# 08-DcMotorEncoder.net
KiCad netlist of a schematic drawn in Altium Designer
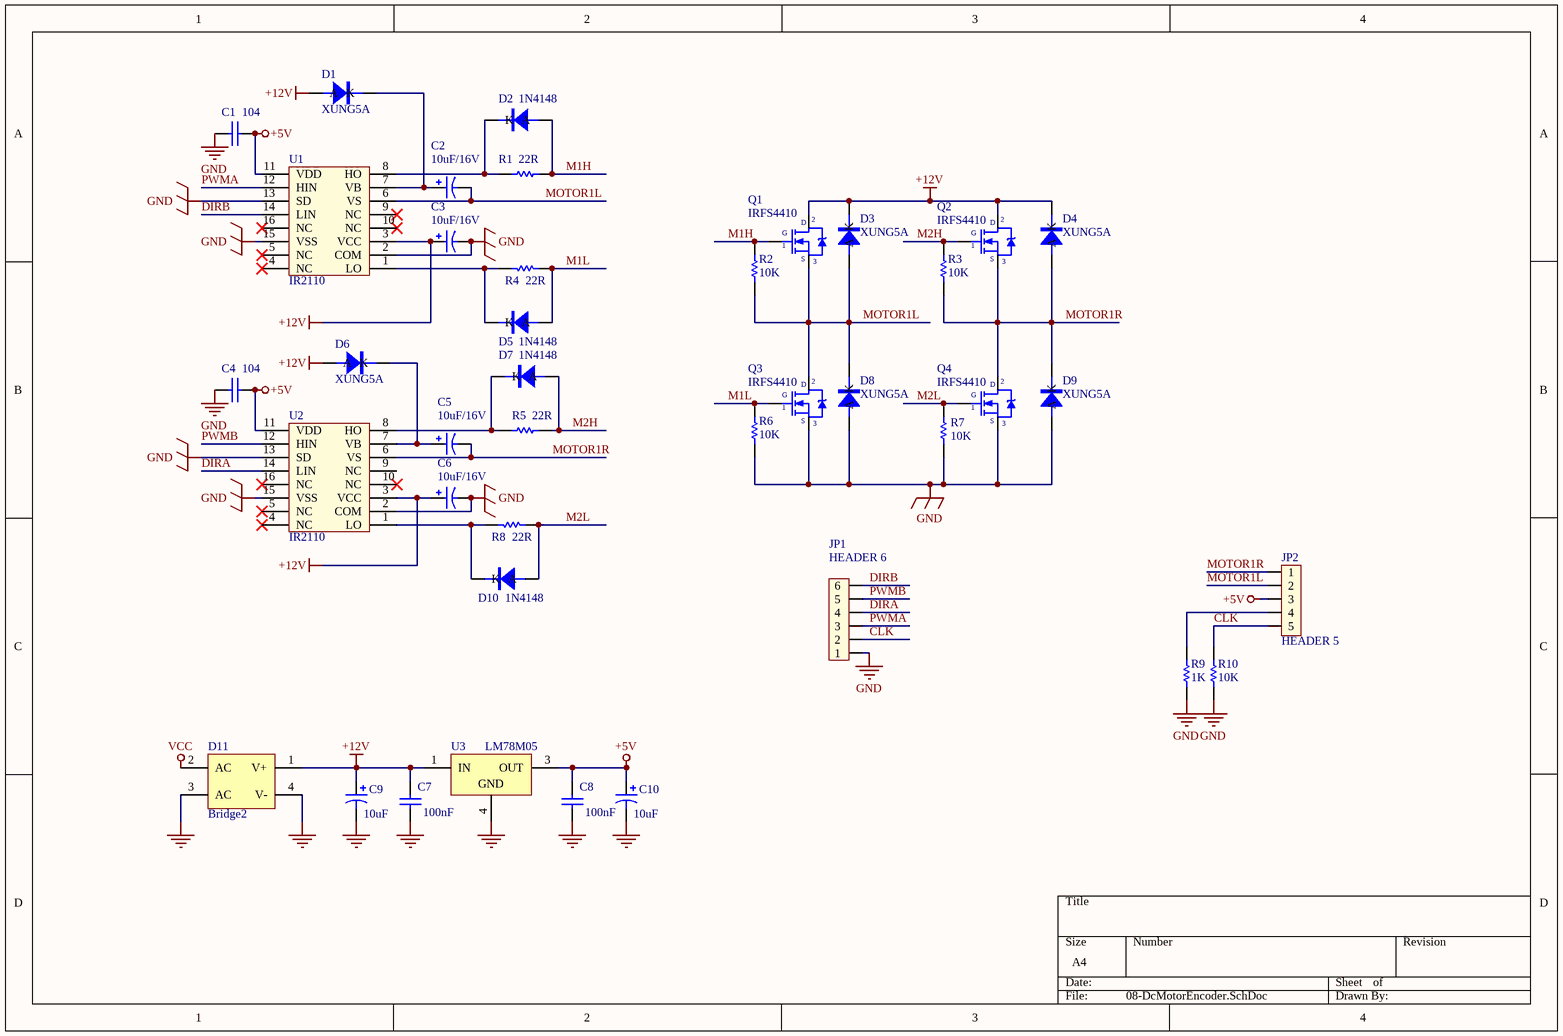
[diagram p0: 08-DcMotorEncoder.SchDoc]

(export (version "E")
  (design (tool "Eeschema 10.0.6"))
  (components
    (comp (ref "C1")
      (value "104")
      (footprint "R-0805")
      (fields (field (name "ALTIUM_VALUE") "104"))
      (libsource (lib "Maker") (part "CAP NP"))
    )
    (comp (ref "C2")
      (value "10uF/16V")
      (footprint "C-TANT-1210")
      (fields (field (name "Comment") "10U16V"))
      (libsource (lib "Maker") (part "CAP POL"))
    )
    (comp (ref "C3")
      (value "10uF/16V")
      (footprint "C-TANT-1210")
      (fields (field (name "Comment") "10U16V"))
      (libsource (lib "Maker") (part "CAP POL"))
    )
    (comp (ref "C4")
      (value "104")
      (footprint "R-0805")
      (fields (field (name "ALTIUM_VALUE") "104"))
      (libsource (lib "Maker") (part "CAP NP"))
    )
    (comp (ref "C5")
      (value "10uF/16V")
      (footprint "C-TANT-1210")
      (fields (field (name "Comment") "10U16V"))
      (libsource (lib "Maker") (part "CAP POL"))
    )
    (comp (ref "C6")
      (value "10uF/16V")
      (footprint "C-TANT-1210")
      (fields (field (name "Comment") "10U16V"))
      (libsource (lib "Maker") (part "CAP POL"))
    )
    (comp (ref "C7")
      (value "100nF")
      (footprint "RAD-0.3")
      (description "Capacitor")
      (fields (field (name "Comment") "104") (field (name "PUBLISHER") "Altium Limited"))
      (libsource (lib "Miscellaneous Devices") (part "Cap"))
    )
    (comp (ref "C8")
      (value "100nF")
      (footprint "RAD-0.3")
      (description "Capacitor")
      (fields (field (name "Comment") "104") (field (name "PUBLISHER") "Altium Limited"))
      (libsource (lib "Miscellaneous Devices") (part "Cap"))
    )
    (comp (ref "C9")
      (value "10uF")
      (footprint "RB7.6-15")
      (description "Polarized Capacitor (Radial)")
      (fields (field (name "Comment") "10uF/16V") (field (name "PUBLISHER") "Altium Limited"))
      (libsource (lib "Miscellaneous Devices") (part "Cap Pol1"))
    )
    (comp (ref "C10")
      (value "10uF")
      (footprint "RB7.6-15")
      (description "Polarized Capacitor (Radial)")
      (fields (field (name "Comment") "10uF/16V") (field (name "PUBLISHER") "Altium Limited"))
      (libsource (lib "Miscellaneous Devices") (part "Cap Pol1"))
    )
    (comp (ref "D1")
      (value "XUNG5A")
      (footprint "D-DO214-AC")
      (fields (field (name "Comment") "1N4007"))
      (libsource (lib "") (part "DIODE_3"))
    )
    (comp (ref "D2") (value "1N4148") (footprint "D-DO213-AA") (libsource (lib "") (part "DIODE_1")))
    (comp (ref "D3")
      (value "XUNG5A")
      (footprint "D-DO214-AC")
      (fields (field (name "Comment") "1N4007"))
      (libsource (lib "Maker") (part "DIODE"))
    )
    (comp (ref "D4")
      (value "XUNG5A")
      (footprint "D-DO214-AC")
      (fields (field (name "Comment") "1N4007"))
      (libsource (lib "Maker") (part "DIODE"))
    )
    (comp (ref "D5") (value "1N4148") (footprint "D-DO213-AA") (libsource (lib "") (part "DIODE_2")))
    (comp (ref "D6")
      (value "XUNG5A")
      (footprint "D-DO214-AC")
      (fields (field (name "Comment") "1N4007"))
      (libsource (lib "") (part "DIODE_3"))
    )
    (comp (ref "D7") (value "1N4148") (footprint "D-DO213-AA") (libsource (lib "") (part "DIODE_1")))
    (comp (ref "D8")
      (value "XUNG5A")
      (footprint "D-DO214-AC")
      (fields (field (name "Comment") "1N4007"))
      (libsource (lib "Maker") (part "DIODE"))
    )
    (comp (ref "D9")
      (value "XUNG5A")
      (footprint "D-DO214-AC")
      (fields (field (name "Comment") "1N4007"))
      (libsource (lib "Maker") (part "DIODE"))
    )
    (comp (ref "D10") (value "1N4148") (footprint "D-DO213-AA") (libsource (lib "") (part "DIODE_2")))
    (comp (ref "D11")
      (value "Bridge2")
      (footprint "D-46_6A")
      (description "Diode Bridge")
      (fields (field (name "PUBLISHER") "Altium Limited"))
      (libsource (lib "Miscellaneous Devices") (part "Bridge2"))
    )
    (comp (ref "JP1")
      (value "HEADER 6")
      (footprint "JP6")
      (description "JP6 PIN")
      (libsource (lib "syhaunguyen") (part "JP6"))
    )
    (comp (ref "JP2")
      (value "HEADER 5")
      (footprint "CONN-XH2.54-5P")
      (libsource (lib "syhaunguyen") (part "JP5"))
    )
    (comp (ref "Q1")
      (value "IRFS4410")
      (footprint "TO-263-3")
      (libsource (lib "doAnTotNghiep2017Lib") (part "IRFS4410"))
    )
    (comp (ref "Q2")
      (value "IRFS4410")
      (footprint "TO-263-3")
      (libsource (lib "doAnTotNghiep2017Lib") (part "IRFS4410"))
    )
    (comp (ref "Q3")
      (value "IRFS4410")
      (footprint "TO-263-3")
      (libsource (lib "doAnTotNghiep2017Lib") (part "IRFS4410"))
    )
    (comp (ref "Q4")
      (value "IRFS4410")
      (footprint "TO-263-3")
      (libsource (lib "doAnTotNghiep2017Lib") (part "IRFS4410"))
    )
    (comp (ref "R1")
      (value "22R")
      (footprint "R-0805")
      (description "Resistor")
      (fields
        (field (name "MANUFACTURER") "Generic Components")
        (field (name "Comment") "22")
        (field (name "PUBLISHER") "Altium Hobart Technology Centre")
      )
      (libsource (lib "Miscellaneous Devices") (part "Res1"))
    )
    (comp (ref "R2")
      (value "10K")
      (footprint "R-0805")
      (description "Resistor")
      (fields
        (field (name "MANUFACTURER") "Generic Components")
        (field (name "PUBLISHER") "Altium Hobart Technology Centre")
      )
      (libsource (lib "Miscellaneous Devices") (part "Res1"))
    )
    (comp (ref "R3")
      (value "10K")
      (footprint "R-0805")
      (description "Resistor")
      (fields
        (field (name "MANUFACTURER") "Generic Components")
        (field (name "PUBLISHER") "Altium Hobart Technology Centre")
      )
      (libsource (lib "Miscellaneous Devices") (part "Res1"))
    )
    (comp (ref "R4")
      (value "22R")
      (footprint "R-0805")
      (description "Resistor")
      (fields
        (field (name "MANUFACTURER") "Generic Components")
        (field (name "Comment") "22")
        (field (name "PUBLISHER") "Altium Hobart Technology Centre")
      )
      (libsource (lib "Miscellaneous Devices") (part "Res1"))
    )
    (comp (ref "R5")
      (value "22R")
      (footprint "R-0805")
      (description "Resistor")
      (fields
        (field (name "MANUFACTURER") "Generic Components")
        (field (name "Comment") "22")
        (field (name "PUBLISHER") "Altium Hobart Technology Centre")
      )
      (libsource (lib "Miscellaneous Devices") (part "Res1"))
    )
    (comp (ref "R6")
      (value "10K")
      (footprint "R-0805")
      (description "Resistor")
      (fields
        (field (name "MANUFACTURER") "Generic Components")
        (field (name "PUBLISHER") "Altium Hobart Technology Centre")
      )
      (libsource (lib "Miscellaneous Devices") (part "Res1"))
    )
    (comp (ref "R7")
      (value "10K")
      (footprint "R-0805")
      (description "Resistor")
      (fields
        (field (name "MANUFACTURER") "Generic Components")
        (field (name "PUBLISHER") "Altium Hobart Technology Centre")
      )
      (libsource (lib "Miscellaneous Devices") (part "Res1"))
    )
    (comp (ref "R8")
      (value "22R")
      (footprint "R-0805")
      (description "Resistor")
      (fields
        (field (name "MANUFACTURER") "Generic Components")
        (field (name "Comment") "22")
        (field (name "PUBLISHER") "Altium Hobart Technology Centre")
      )
      (libsource (lib "Miscellaneous Devices") (part "Res1"))
    )
    (comp (ref "R9")
      (value "1K")
      (footprint "R-0805")
      (description "Resistor")
      (fields
        (field (name "MANUFACTURER") "Generic Components")
        (field (name "PUBLISHER") "Altium Hobart Technology Centre")
      )
      (libsource (lib "Miscellaneous Devices") (part "Res1"))
    )
    (comp (ref "R10")
      (value "10K")
      (footprint "R-0805")
      (description "Resistor")
      (fields
        (field (name "MANUFACTURER") "Generic Components")
        (field (name "Comment") "1K")
        (field (name "PUBLISHER") "Altium Hobart Technology Centre")
      )
      (libsource (lib "Miscellaneous Devices") (part "Res1"))
    )
    (comp (ref "U1")
      (value "IR2110")
      (footprint "SOIC-16-W")
      (libsource (lib "doAnTotNghiep2017Lib") (part "IR2110"))
    )
    (comp (ref "U2")
      (value "IR2110")
      (footprint "SOIC-16-W")
      (libsource (lib "doAnTotNghiep2017Lib") (part "IR2110"))
    )
    (comp (ref "U3")
      (value "LM78M05")
      (footprint "NDP0003B_M")
      (description "3-Terminal Positive Voltage Regulators, 3-pin TO-252")
      (fields (field (name "MANUFACTURER") "Texas Instruments") (field (name "Comment") "LM78M05CDTX"))
      (libsource (lib "Altium Content Vault") (part "CMP-0062-00204-3"))
    )
  )
  (nets
    (net (code "1") (name "+5V") (class "Default")
      (node (ref "C1") (pin "2") (pintype "passive"))
      (node (ref "C10") (pin "1") (pinfunction "1_1") (pintype "passive"))
      (node (ref "C4") (pin "2") (pintype "passive"))
      (node (ref "C8") (pin "1") (pinfunction "1_1") (pintype "passive"))
      (node (ref "JP2") (pin "3") (pinfunction "3_3") (pintype "passive"))
      (node (ref "U1") (pin "11") (pinfunction "VDD_11") (pintype "passive"))
      (node (ref "U2") (pin "11") (pinfunction "VDD_11") (pintype "passive"))
      (node (ref "U3") (pin "3") (pinfunction "OUT_3") (pintype "power_in"))
    )
    (net (code "2") (name "+12V") (class "Default")
      (node (ref "C3") (pin "1") (pinfunction "1_1") (pintype "passive"))
      (node (ref "C6") (pin "1") (pinfunction "1_1") (pintype "passive"))
      (node (ref "C7") (pin "1") (pinfunction "1_1") (pintype "passive"))
      (node (ref "C9") (pin "1") (pinfunction "1_1") (pintype "passive"))
      (node (ref "D1") (pin "1") (pinfunction "A_1") (pintype "passive"))
      (node (ref "D11") (pin "1") (pinfunction "V+_1") (pintype "passive"))
      (node (ref "D3") (pin "2") (pinfunction "K_2") (pintype "passive"))
      (node (ref "D4") (pin "2") (pinfunction "K_2") (pintype "passive"))
      (node (ref "D6") (pin "1") (pinfunction "A_1") (pintype "passive"))
      (node (ref "Q1") (pin "2") (pinfunction "D_2") (pintype "passive"))
      (node (ref "Q2") (pin "2") (pinfunction "D_2") (pintype "passive"))
      (node (ref "U1") (pin "3") (pinfunction "VCC_3") (pintype "passive"))
      (node (ref "U2") (pin "3") (pinfunction "VCC_3") (pintype "passive"))
      (node (ref "U3") (pin "1") (pinfunction "IN_1") (pintype "power_in"))
    )
    (net (code "3") (name "/CLK") (class "Default")
      (node (ref "JP1") (pin "2") (pinfunction "2_2") (pintype "passive"))
      (node (ref "JP2") (pin "5") (pinfunction "5_5") (pintype "passive"))
      (node (ref "R10") (pin "2") (pinfunction "2_2") (pintype "passive"))
    )
    (net (code "4") (name "/DIRA") (class "Default")
      (node (ref "JP1") (pin "4") (pinfunction "4_4") (pintype "passive"))
      (node (ref "U2") (pin "14") (pinfunction "LIN_14") (pintype "passive"))
    )
    (net (code "5") (name "/DIRB") (class "Default")
      (node (ref "JP1") (pin "6") (pinfunction "6_6") (pintype "passive"))
      (node (ref "U1") (pin "14") (pinfunction "LIN_14") (pintype "passive"))
    )
    (net (code "6") (name "/M1H") (class "Default")
      (node (ref "D2") (pin "1") (pinfunction "A_1") (pintype "passive"))
      (node (ref "Q1") (pin "1") (pinfunction "G_1") (pintype "passive"))
      (node (ref "R1") (pin "2") (pinfunction "2_2") (pintype "passive"))
      (node (ref "R2") (pin "2") (pinfunction "2_2") (pintype "passive"))
    )
    (net (code "7") (name "/M1L") (class "Default")
      (node (ref "D5") (pin "1") (pinfunction "A_1") (pintype "passive"))
      (node (ref "Q3") (pin "1") (pinfunction "G_1") (pintype "passive"))
      (node (ref "R4") (pin "2") (pinfunction "2_2") (pintype "passive"))
      (node (ref "R6") (pin "2") (pinfunction "2_2") (pintype "passive"))
    )
    (net (code "8") (name "/M2H") (class "Default")
      (node (ref "D7") (pin "1") (pinfunction "A_1") (pintype "passive"))
      (node (ref "Q2") (pin "1") (pinfunction "G_1") (pintype "passive"))
      (node (ref "R3") (pin "2") (pinfunction "2_2") (pintype "passive"))
      (node (ref "R5") (pin "2") (pinfunction "2_2") (pintype "passive"))
    )
    (net (code "9") (name "/M2L") (class "Default")
      (node (ref "D10") (pin "1") (pinfunction "A_1") (pintype "passive"))
      (node (ref "Q4") (pin "1") (pinfunction "G_1") (pintype "passive"))
      (node (ref "R7") (pin "2") (pinfunction "2_2") (pintype "passive"))
      (node (ref "R8") (pin "2") (pinfunction "2_2") (pintype "passive"))
    )
    (net (code "10") (name "/MOTOR1L") (class "Default")
      (node (ref "C2") (pin "2") (pinfunction "2_2") (pintype "passive"))
      (node (ref "D3") (pin "1") (pinfunction "A_1") (pintype "passive"))
      (node (ref "D8") (pin "2") (pinfunction "K_2") (pintype "passive"))
      (node (ref "JP2") (pin "2") (pinfunction "2_2") (pintype "passive"))
      (node (ref "Q1") (pin "3") (pinfunction "S_3") (pintype "passive"))
      (node (ref "Q3") (pin "2") (pinfunction "D_2") (pintype "passive"))
      (node (ref "R2") (pin "1") (pinfunction "1_1") (pintype "passive"))
      (node (ref "U1") (pin "6") (pinfunction "VS_6") (pintype "passive"))
    )
    (net (code "11") (name "/MOTOR1R") (class "Default")
      (node (ref "C5") (pin "2") (pinfunction "2_2") (pintype "passive"))
      (node (ref "D4") (pin "1") (pinfunction "A_1") (pintype "passive"))
      (node (ref "D9") (pin "2") (pinfunction "K_2") (pintype "passive"))
      (node (ref "JP2") (pin "1") (pinfunction "1_1") (pintype "passive"))
      (node (ref "Q2") (pin "3") (pinfunction "S_3") (pintype "passive"))
      (node (ref "Q4") (pin "2") (pinfunction "D_2") (pintype "passive"))
      (node (ref "R3") (pin "1") (pinfunction "1_1") (pintype "passive"))
      (node (ref "U2") (pin "6") (pinfunction "VS_6") (pintype "passive"))
    )
    (net (code "12") (name "/PWMA") (class "Default")
      (node (ref "JP1") (pin "3") (pinfunction "3_3") (pintype "passive"))
      (node (ref "U1") (pin "12") (pinfunction "HIN_12") (pintype "passive"))
    )
    (net (code "13") (name "/PWMB") (class "Default")
      (node (ref "JP1") (pin "5") (pinfunction "5_5") (pintype "passive"))
      (node (ref "U2") (pin "12") (pinfunction "HIN_12") (pintype "passive"))
    )
    (net (code "14") (name "GND") (class "Default")
      (node (ref "C1") (pin "1") (pintype "passive"))
      (node (ref "C10") (pin "2") (pinfunction "2_2") (pintype "passive"))
      (node (ref "C3") (pin "2") (pinfunction "2_2") (pintype "passive"))
      (node (ref "C4") (pin "1") (pintype "passive"))
      (node (ref "C6") (pin "2") (pinfunction "2_2") (pintype "passive"))
      (node (ref "C7") (pin "2") (pinfunction "2_2") (pintype "passive"))
      (node (ref "C8") (pin "2") (pinfunction "2_2") (pintype "passive"))
      (node (ref "C9") (pin "2") (pinfunction "2_2") (pintype "passive"))
      (node (ref "D11") (pin "3") (pinfunction "AC_3") (pintype "passive"))
      (node (ref "D11") (pin "4") (pinfunction "V-_4") (pintype "passive"))
      (node (ref "D8") (pin "1") (pinfunction "A_1") (pintype "passive"))
      (node (ref "D9") (pin "1") (pinfunction "A_1") (pintype "passive"))
      (node (ref "JP1") (pin "1") (pinfunction "1_1") (pintype "passive"))
      (node (ref "Q3") (pin "3") (pinfunction "S_3") (pintype "passive"))
      (node (ref "Q4") (pin "3") (pinfunction "S_3") (pintype "passive"))
      (node (ref "R10") (pin "1") (pinfunction "1_1") (pintype "passive"))
      (node (ref "R6") (pin "1") (pinfunction "1_1") (pintype "passive"))
      (node (ref "R7") (pin "1") (pinfunction "1_1") (pintype "passive"))
      (node (ref "R9") (pin "1") (pinfunction "1_1") (pintype "passive"))
      (node (ref "U1") (pin "13") (pinfunction "SD_13") (pintype "passive"))
      (node (ref "U1") (pin "15") (pinfunction "VSS_15") (pintype "passive"))
      (node (ref "U1") (pin "2") (pinfunction "COM_2") (pintype "passive"))
      (node (ref "U2") (pin "13") (pinfunction "SD_13") (pintype "passive"))
      (node (ref "U2") (pin "15") (pinfunction "VSS_15") (pintype "passive"))
      (node (ref "U2") (pin "2") (pinfunction "COM_2") (pintype "passive"))
      (node (ref "U3") (pin "4") (pinfunction "GND_4") (pintype "power_in"))
    )
    (net (code "15") (name "Net-(D1-K)") (class "Default")
      (node (ref "C2") (pin "1") (pinfunction "1_1") (pintype "passive"))
      (node (ref "D1") (pin "2") (pinfunction "K_2") (pintype "passive"))
      (node (ref "U1") (pin "7") (pinfunction "VB_7") (pintype "passive"))
    )
    (net (code "16") (name "Net-(D2-K)") (class "Default")
      (node (ref "D2") (pin "2") (pinfunction "K_2") (pintype "passive"))
      (node (ref "R1") (pin "1") (pinfunction "1_1") (pintype "passive"))
      (node (ref "U1") (pin "8") (pinfunction "HO_8") (pintype "passive"))
    )
    (net (code "17") (name "Net-(D5-K)") (class "Default")
      (node (ref "D5") (pin "2") (pinfunction "K_2") (pintype "passive"))
      (node (ref "R4") (pin "1") (pinfunction "1_1") (pintype "passive"))
      (node (ref "U1") (pin "1") (pinfunction "LO_1") (pintype "passive"))
    )
    (net (code "18") (name "Net-(D6-K)") (class "Default")
      (node (ref "C5") (pin "1") (pinfunction "1_1") (pintype "passive"))
      (node (ref "D6") (pin "2") (pinfunction "K_2") (pintype "passive"))
      (node (ref "U2") (pin "7") (pinfunction "VB_7") (pintype "passive"))
    )
    (net (code "19") (name "Net-(D7-K)") (class "Default")
      (node (ref "D7") (pin "2") (pinfunction "K_2") (pintype "passive"))
      (node (ref "R5") (pin "1") (pinfunction "1_1") (pintype "passive"))
      (node (ref "U2") (pin "8") (pinfunction "HO_8") (pintype "passive"))
    )
    (net (code "20") (name "Net-(D10-K)") (class "Default")
      (node (ref "D10") (pin "2") (pinfunction "K_2") (pintype "passive"))
      (node (ref "R8") (pin "1") (pinfunction "1_1") (pintype "passive"))
      (node (ref "U2") (pin "1") (pinfunction "LO_1") (pintype "passive"))
    )
    (net (code "21") (name "Net-(JP2-Pad4)") (class "Default")
      (node (ref "JP2") (pin "4") (pinfunction "4_4") (pintype "passive"))
      (node (ref "R9") (pin "2") (pinfunction "2_2") (pintype "passive"))
    )
    (net (code "22") (name "VCC") (class "Default")
      (node (ref "D11") (pin "2") (pinfunction "AC_2") (pintype "passive"))
    )
    (net (code "23") (name "unconnected-(U1-NC-Pad4)") (class "Default")
      (node (ref "U1") (pin "4") (pinfunction "NC_4") (pintype "passive+no_connect"))
    )
    (net (code "24") (name "unconnected-(U1-NC-Pad5)") (class "Default")
      (node (ref "U1") (pin "5") (pinfunction "NC_5") (pintype "passive+no_connect"))
    )
    (net (code "25") (name "unconnected-(U1-NC-Pad9)") (class "Default")
      (node (ref "U1") (pin "9") (pinfunction "NC_9") (pintype "passive+no_connect"))
    )
    (net (code "26") (name "unconnected-(U1-NC-Pad10)") (class "Default")
      (node (ref "U1") (pin "10") (pinfunction "NC_10") (pintype "passive+no_connect"))
    )
    (net (code "27") (name "unconnected-(U1-NC-Pad16)") (class "Default")
      (node (ref "U1") (pin "16") (pinfunction "NC_16") (pintype "passive+no_connect"))
    )
    (net (code "28") (name "unconnected-(U2-NC-Pad4)") (class "Default")
      (node (ref "U2") (pin "4") (pinfunction "NC_4") (pintype "passive+no_connect"))
    )
    (net (code "29") (name "unconnected-(U2-NC-Pad5)") (class "Default")
      (node (ref "U2") (pin "5") (pinfunction "NC_5") (pintype "passive+no_connect"))
    )
    (net (code "30") (name "unconnected-(U2-NC-Pad9)") (class "Default")
      (node (ref "U2") (pin "9") (pinfunction "NC_9") (pintype "passive"))
    )
    (net (code "31") (name "unconnected-(U2-NC-Pad10)") (class "Default")
      (node (ref "U2") (pin "10") (pinfunction "NC_10") (pintype "passive+no_connect"))
    )
    (net (code "32") (name "unconnected-(U2-NC-Pad16)") (class "Default")
      (node (ref "U2") (pin "16") (pinfunction "NC_16") (pintype "passive+no_connect"))
    )
  )
)
